# DSO_ADC.net
KiCad netlist of a schematic drawn in Altium Designer
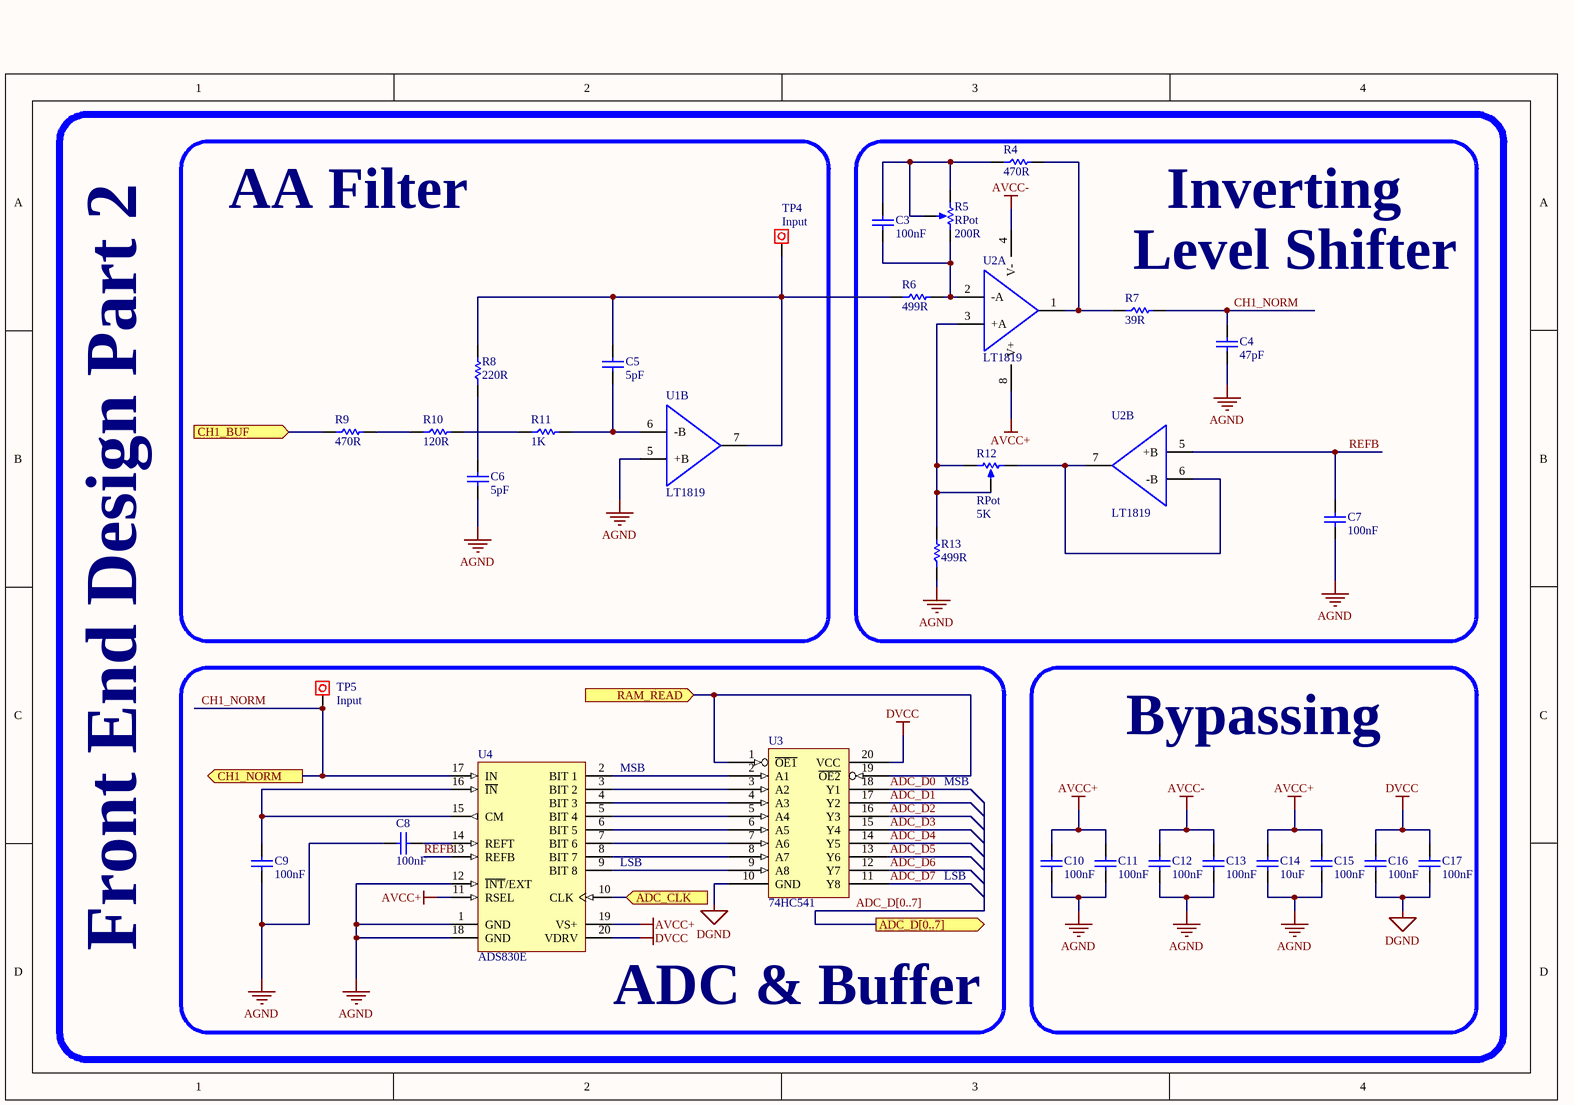
[diagram p0: DSO_ADC.SchDoc]

(export (version "E")
  (design (tool "Eeschema 10.0.6"))
  (components
    (comp (ref "C3")
      (value "100nF")
      (footprint "0805C")
      (description "Capacitor")
      (fields (field (name "REVIEWED BY") "RM - 2018/08/05"))
      (libsource (lib "DSO") (part "C"))
    )
    (comp (ref "C4")
      (value "47pF")
      (footprint "0805C")
      (description "Capacitor")
      (fields (field (name "REVIEWED BY") "RM - 2018/08/05"))
      (libsource (lib "DSO") (part "C"))
    )
    (comp (ref "C5")
      (value "5pF")
      (footprint "0805C")
      (description "Capacitor")
      (fields (field (name "REVIEWED BY") "RM - 2018/08/05"))
      (libsource (lib "DSO") (part "C"))
    )
    (comp (ref "C6")
      (value "5pF")
      (footprint "0805C")
      (description "Capacitor")
      (fields (field (name "REVIEWED BY") "RM - 2018/08/05"))
      (libsource (lib "DSO") (part "C"))
    )
    (comp (ref "C7")
      (value "100nF")
      (footprint "0805C")
      (description "Capacitor")
      (fields (field (name "REVIEWED BY") "RM - 2018/08/05"))
      (libsource (lib "DSO") (part "C"))
    )
    (comp (ref "C8")
      (value "100nF")
      (footprint "0805C")
      (description "Capacitor")
      (fields (field (name "REVIEWED BY") "RM - 2018/08/05"))
      (libsource (lib "DSO") (part "C"))
    )
    (comp (ref "C9")
      (value "100nF")
      (footprint "0805C")
      (description "Capacitor")
      (fields (field (name "REVIEWED BY") "RM - 2018/08/05"))
      (libsource (lib "DSO") (part "C"))
    )
    (comp (ref "C10")
      (value "100nF")
      (footprint "0805C")
      (description "Capacitor")
      (fields (field (name "REVIEWED BY") "RM - 2018/08/05"))
      (libsource (lib "DSO") (part "C"))
    )
    (comp (ref "C11")
      (value "100nF")
      (footprint "0805C")
      (description "Capacitor")
      (fields (field (name "REVIEWED BY") "RM - 2018/08/05"))
      (libsource (lib "DSO") (part "C"))
    )
    (comp (ref "C12")
      (value "100nF")
      (footprint "0805C")
      (description "Capacitor")
      (fields (field (name "REVIEWED BY") "RM - 2018/08/05"))
      (libsource (lib "DSO") (part "C"))
    )
    (comp (ref "C13")
      (value "100nF")
      (footprint "0805C")
      (description "Capacitor")
      (fields (field (name "REVIEWED BY") "RM - 2018/08/05"))
      (libsource (lib "DSO") (part "C"))
    )
    (comp (ref "C14")
      (value "10uF")
      (footprint "0805C")
      (description "Capacitor")
      (fields (field (name "REVIEWED BY") "RM - 2018/08/05"))
      (libsource (lib "DSO") (part "C"))
    )
    (comp (ref "C15")
      (value "100nF")
      (footprint "0805C")
      (description "Capacitor")
      (fields (field (name "REVIEWED BY") "RM - 2018/08/05"))
      (libsource (lib "DSO") (part "C"))
    )
    (comp (ref "C16")
      (value "100nF")
      (footprint "0805C")
      (description "Capacitor")
      (fields (field (name "REVIEWED BY") "RM - 2018/08/05"))
      (libsource (lib "DSO") (part "C"))
    )
    (comp (ref "C17")
      (value "100nF")
      (footprint "0805C")
      (description "Capacitor")
      (fields (field (name "REVIEWED BY") "RM - 2018/08/05"))
      (libsource (lib "DSO") (part "C"))
    )
    (comp (ref "R4")
      (value "470R")
      (footprint "0805")
      (description "Resistor")
      (fields (field (name "REVIEWED BY") "RM - 2018/08/05"))
      (libsource (lib "DSO") (part "R"))
    )
    (comp (ref "R5")
      (value "RPot")
      (footprint "VR5")
      (description "Potentiometer")
      (fields (field (name "ALTIUM_VALUE") "200R") (field (name "PUBLISHER") "Altium Limited"))
      (libsource (lib "DSO") (part "RPot"))
    )
    (comp (ref "R6")
      (value "499R")
      (footprint "0805")
      (description "Resistor")
      (fields (field (name "REVIEWED BY") "RM - 2018/08/05"))
      (libsource (lib "DSO") (part "R"))
    )
    (comp (ref "R7")
      (value "39R")
      (footprint "0805")
      (description "Resistor")
      (fields (field (name "REVIEWED BY") "RM - 2018/08/05"))
      (libsource (lib "DSO") (part "R"))
    )
    (comp (ref "R8")
      (value "220R")
      (footprint "0805")
      (description "Resistor")
      (fields (field (name "REVIEWED BY") "RM - 2018/08/05"))
      (libsource (lib "DSO") (part "R"))
    )
    (comp (ref "R9")
      (value "470R")
      (footprint "0805")
      (description "Resistor")
      (fields (field (name "REVIEWED BY") "RM - 2018/08/05"))
      (libsource (lib "DSO") (part "R"))
    )
    (comp (ref "R10")
      (value "120R")
      (footprint "0805")
      (description "Resistor")
      (fields (field (name "REVIEWED BY") "RM - 2018/08/05"))
      (libsource (lib "DSO") (part "R"))
    )
    (comp (ref "R11")
      (value "1K")
      (footprint "0805")
      (description "Resistor")
      (fields (field (name "REVIEWED BY") "RM - 2018/08/05"))
      (libsource (lib "DSO") (part "R"))
    )
    (comp (ref "R12")
      (value "RPot")
      (footprint "VR5")
      (description "Potentiometer")
      (fields (field (name "ALTIUM_VALUE") "5K") (field (name "PUBLISHER") "Altium Limited"))
      (libsource (lib "DSO") (part "RPot"))
    )
    (comp (ref "R13")
      (value "499R")
      (footprint "0805")
      (description "Resistor")
      (fields (field (name "REVIEWED BY") "RM - 2018/08/05"))
      (libsource (lib "DSO") (part "R"))
    )
    (comp (ref "TP4")
      (value "Input")
      (footprint "Testpoin")
      (description "Pad")
      (fields (field (name "Comment") "INPUT"))
      (libsource (lib "DSO") (part "Test Point"))
    )
    (comp (ref "TP5")
      (value "Input")
      (footprint "Testpoin")
      (description "Pad")
      (fields (field (name "Comment") "INPUT"))
      (libsource (lib "DSO") (part "Test Point"))
    )
    (comp (ref "U1")
      (value "LT1819")
      (footprint "SOIC-8")
      (description "OpAmp High Frequency Dual")
      (fields (field (name "REVIEWED BY") "RM - 2018/08/05"))
      (libsource (lib "DSO") (part "LT1819"))
    )
    (comp (ref "U2")
      (value "LT1819")
      (footprint "SOIC-8")
      (description "OpAmp High Frequency Dual")
      (fields (field (name "REVIEWED BY") "RM - 2018/08/05"))
      (libsource (lib "DSO") (part "LT1819"))
    )
    (comp (ref "U3")
      (value "74HC541")
      (footprint "SOT163-1_N")
      (description "(ADV) Octal Buffer, Line Driver")
      (fields (field (name "REVIEWED BY") "RM - 2018/08/05"))
      (libsource (lib "DSO") (part "74HC541"))
    )
    (comp (ref "U4")
      (value "ADS830E")
      (footprint "TI-DBQ20_L")
      (fields (field (name "REVIEWED BY") "RM - 2018/08/05"))
      (libsource (lib "DSO") (part "ADS830E"))
    )
  )
  (nets
    (net (code "1") (name "/ADC_CLK") (class "Default")
      (node (ref "U4") (pin "10") (pinfunction "CLK_10") (pintype "input"))
    )
    (net (code "2") (name "/ADC_D0") (class "Default")
      (node (ref "U3") (pin "18") (pinfunction "Y1_18") (pintype "tri_state"))
    )
    (net (code "3") (name "/ADC_D1") (class "Default")
      (node (ref "U3") (pin "17") (pinfunction "Y2_17") (pintype "tri_state"))
    )
    (net (code "4") (name "/ADC_D2") (class "Default")
      (node (ref "U3") (pin "16") (pinfunction "Y3_16") (pintype "tri_state"))
    )
    (net (code "5") (name "/ADC_D3") (class "Default")
      (node (ref "U3") (pin "15") (pinfunction "Y4_15") (pintype "tri_state"))
    )
    (net (code "6") (name "/ADC_D4") (class "Default")
      (node (ref "U3") (pin "14") (pinfunction "Y5_14") (pintype "tri_state"))
    )
    (net (code "7") (name "/ADC_D5") (class "Default")
      (node (ref "U3") (pin "13") (pinfunction "Y6_13") (pintype "tri_state"))
    )
    (net (code "8") (name "/ADC_D6") (class "Default")
      (node (ref "U3") (pin "12") (pinfunction "Y7_12") (pintype "tri_state"))
    )
    (net (code "9") (name "/ADC_D7") (class "Default")
      (node (ref "U3") (pin "11") (pinfunction "Y8_11") (pintype "tri_state"))
    )
    (net (code "11") (name "/CH1_BUF") (class "Default") (node (ref "R9") (pin "1") (pintype "passive")))
    (net (code "12") (name "/CH1_NORM") (class "Default")
      (node (ref "C4") (pin "1") (pinfunction "1_1") (pintype "passive"))
      (node (ref "R7") (pin "2") (pintype "passive"))
      (node (ref "TP5") (pin "1") (pintype "passive"))
      (node (ref "U4") (pin "17") (pinfunction "IN_17") (pintype "input"))
    )
    (net (code "13") (name "/RAM_READ") (class "Default")
      (node (ref "U3") (pin "1") (pinfunction "~{OE1}_1") (pintype "input"))
      (node (ref "U3") (pin "19") (pinfunction "~{OE2}_19") (pintype "input"))
    )
    (net (code "14") (name "/REFB") (class "Default")
      (node (ref "C7") (pin "1") (pinfunction "1_1") (pintype "passive"))
      (node (ref "U2") (pin "5") (pinfunction "+B_5") (pintype "passive"))
      (node (ref "U4") (pin "13") (pinfunction "REFB_13") (pintype "input"))
    )
    (net (code "15") (name "AGND") (class "Default")
      (node (ref "C10") (pin "1") (pinfunction "1_1") (pintype "passive"))
      (node (ref "C11") (pin "1") (pinfunction "1_1") (pintype "passive"))
      (node (ref "C12") (pin "1") (pinfunction "1_1") (pintype "passive"))
      (node (ref "C13") (pin "1") (pinfunction "1_1") (pintype "passive"))
      (node (ref "C14") (pin "1") (pinfunction "1_1") (pintype "passive"))
      (node (ref "C15") (pin "1") (pinfunction "1_1") (pintype "passive"))
      (node (ref "C4") (pin "2") (pinfunction "2_2") (pintype "passive"))
      (node (ref "C6") (pin "2") (pinfunction "2_2") (pintype "passive"))
      (node (ref "C7") (pin "2") (pinfunction "2_2") (pintype "passive"))
      (node (ref "C8") (pin "2") (pinfunction "2_2") (pintype "passive"))
      (node (ref "C9") (pin "1") (pinfunction "1_1") (pintype "passive"))
      (node (ref "R13") (pin "1") (pintype "passive"))
      (node (ref "U1") (pin "5") (pinfunction "+B_5") (pintype "passive"))
      (node (ref "U4") (pin "1") (pinfunction "GND_1") (pintype "power_in"))
      (node (ref "U4") (pin "12") (pinfunction "~{INT}/EXT_12") (pintype "input"))
      (node (ref "U4") (pin "18") (pinfunction "GND_18") (pintype "power_in"))
    )
    (net (code "16") (name "AVCC+") (class "Default")
      (node (ref "C10") (pin "2") (pinfunction "2_2") (pintype "passive"))
      (node (ref "C11") (pin "2") (pinfunction "2_2") (pintype "passive"))
      (node (ref "C14") (pin "2") (pinfunction "2_2") (pintype "passive"))
      (node (ref "C15") (pin "2") (pinfunction "2_2") (pintype "passive"))
      (node (ref "U2") (pin "8") (pinfunction "V+_8") (pintype "passive"))
      (node (ref "U4") (pin "11") (pinfunction "RSEL_11") (pintype "input"))
      (node (ref "U4") (pin "19") (pinfunction "VS+_19") (pintype "power_in"))
    )
    (net (code "17") (name "AVCC-") (class "Default")
      (node (ref "C12") (pin "2") (pinfunction "2_2") (pintype "passive"))
      (node (ref "C13") (pin "2") (pinfunction "2_2") (pintype "passive"))
      (node (ref "U2") (pin "4") (pinfunction "V-_4") (pintype "passive"))
    )
    (net (code "18") (name "DGND") (class "Default")
      (node (ref "C16") (pin "1") (pinfunction "1_1") (pintype "passive"))
      (node (ref "C17") (pin "1") (pinfunction "1_1") (pintype "passive"))
      (node (ref "U3") (pin "10") (pinfunction "GND_10") (pintype "power_in"))
    )
    (net (code "19") (name "DVCC") (class "Default")
      (node (ref "C16") (pin "2") (pinfunction "2_2") (pintype "passive"))
      (node (ref "C17") (pin "2") (pinfunction "2_2") (pintype "passive"))
      (node (ref "U3") (pin "20") (pinfunction "VCC_20") (pintype "power_in"))
      (node (ref "U4") (pin "20") (pinfunction "VDRV_20") (pintype "power_in"))
    )
    (net (code "20") (name "Net-(C6-Pad1)") (class "Default")
      (node (ref "C6") (pin "1") (pinfunction "1_1") (pintype "passive"))
      (node (ref "R8") (pin "1") (pintype "passive"))
    )
    (net (code "21") (name "Net-(R5-BOT)") (class "Default")
      (node (ref "C3") (pin "2") (pinfunction "2_2") (pintype "passive"))
      (node (ref "R5") (pin "3") (pinfunction "BOT_3") (pintype "passive"))
      (node (ref "R6") (pin "2") (pintype "passive"))
      (node (ref "U2") (pin "2") (pinfunction "-A_2") (pintype "passive"))
    )
    (net (code "22") (name "Net-(R5-TAP)") (class "Default")
      (node (ref "C3") (pin "1") (pinfunction "1_1") (pintype "passive"))
      (node (ref "R4") (pin "1") (pintype "passive"))
      (node (ref "R5") (pin "1") (pinfunction "TOP_1") (pintype "passive"))
      (node (ref "R5") (pin "2") (pinfunction "TAP_2") (pintype "passive"))
    )
    (net (code "23") (name "Net-(R10-Pad1)") (class "Default")
      (node (ref "R10") (pin "1") (pintype "passive"))
      (node (ref "R9") (pin "2") (pintype "passive"))
    )
    (net (code "24") (name "Net-(R10-Pad2)") (class "Default")
      (node (ref "R10") (pin "2") (pintype "passive"))
      (node (ref "R11") (pin "1") (pintype "passive"))
    )
    (net (code "25") (name "Net-(R12-BOT)") (class "Default")
      (node (ref "R12") (pin "3") (pinfunction "BOT_3") (pintype "passive"))
      (node (ref "U2") (pin "6") (pinfunction "-B_6") (pintype "passive"))
      (node (ref "U2") (pin "7") (pinfunction "OUTB_7") (pintype "passive"))
    )
    (net (code "26") (name "Net-(R12-TAP)") (class "Default")
      (node (ref "R12") (pin "1") (pinfunction "TOP_1") (pintype "passive"))
      (node (ref "R12") (pin "2") (pinfunction "TAP_2") (pintype "passive"))
      (node (ref "R13") (pin "2") (pintype "passive"))
      (node (ref "U2") (pin "3") (pinfunction "+A_3") (pintype "passive"))
    )
    (net (code "27") (name "Net-(U1B--B)") (class "Default")
      (node (ref "C5") (pin "2") (pinfunction "2_2") (pintype "passive"))
      (node (ref "R11") (pin "2") (pintype "passive"))
      (node (ref "U1") (pin "6") (pinfunction "-B_6") (pintype "passive"))
    )
    (net (code "28") (name "Net-(U1B-OUTB)") (class "Default")
      (node (ref "C5") (pin "1") (pinfunction "1_1") (pintype "passive"))
      (node (ref "R6") (pin "1") (pintype "passive"))
      (node (ref "R8") (pin "2") (pintype "passive"))
      (node (ref "TP4") (pin "1") (pintype "passive"))
      (node (ref "U1") (pin "7") (pinfunction "OUTB_7") (pintype "passive"))
    )
    (net (code "29") (name "Net-(U2A-OUTA)") (class "Default")
      (node (ref "R4") (pin "2") (pintype "passive"))
      (node (ref "R7") (pin "1") (pintype "passive"))
      (node (ref "U2") (pin "1") (pinfunction "OUTA_1") (pintype "passive"))
    )
    (net (code "30") (name "Net-(U3-A1)") (class "Default")
      (node (ref "U3") (pin "2") (pinfunction "A1_2") (pintype "input"))
      (node (ref "U4") (pin "2") (pinfunction "BIT_1_2") (pintype "tri_state"))
    )
    (net (code "31") (name "Net-(U3-A2)") (class "Default")
      (node (ref "U3") (pin "3") (pinfunction "A2_3") (pintype "input"))
      (node (ref "U4") (pin "3") (pinfunction "BIT_2_3") (pintype "tri_state"))
    )
    (net (code "32") (name "Net-(U3-A3)") (class "Default")
      (node (ref "U3") (pin "4") (pinfunction "A3_4") (pintype "input"))
      (node (ref "U4") (pin "4") (pinfunction "BIT_3_4") (pintype "tri_state"))
    )
    (net (code "33") (name "Net-(U3-A4)") (class "Default")
      (node (ref "U3") (pin "5") (pinfunction "A4_5") (pintype "input"))
      (node (ref "U4") (pin "5") (pinfunction "BIT_4_5") (pintype "tri_state"))
    )
    (net (code "34") (name "Net-(U3-A5)") (class "Default")
      (node (ref "U3") (pin "6") (pinfunction "A5_6") (pintype "input"))
      (node (ref "U4") (pin "6") (pinfunction "BIT_5_6") (pintype "tri_state"))
    )
    (net (code "35") (name "Net-(U3-A6)") (class "Default")
      (node (ref "U3") (pin "7") (pinfunction "A6_7") (pintype "input"))
      (node (ref "U4") (pin "7") (pinfunction "BIT_6_7") (pintype "tri_state"))
    )
    (net (code "36") (name "Net-(U3-A7)") (class "Default")
      (node (ref "U3") (pin "8") (pinfunction "A7_8") (pintype "input"))
      (node (ref "U4") (pin "8") (pinfunction "BIT_7_8") (pintype "tri_state"))
    )
    (net (code "37") (name "Net-(U3-A8)") (class "Default")
      (node (ref "U3") (pin "9") (pinfunction "A8_9") (pintype "input"))
      (node (ref "U4") (pin "9") (pinfunction "BIT_8_9") (pintype "tri_state"))
    )
    (net (code "38") (name "Net-(U4-CM)") (class "Default")
      (node (ref "C9") (pin "2") (pinfunction "2_2") (pintype "passive"))
      (node (ref "U4") (pin "15") (pinfunction "CM_15") (pintype "output"))
      (node (ref "U4") (pin "16") (pinfunction "~{IN}_16") (pintype "input"))
    )
    (net (code "39") (name "Net-(U4-REFT)") (class "Default")
      (node (ref "C8") (pin "1") (pinfunction "1_1") (pintype "passive"))
      (node (ref "U4") (pin "14") (pinfunction "REFT_14") (pintype "input"))
    )
  )
)
